# AGCON.net
KiCad netlist of a schematic drawn in EAGLE
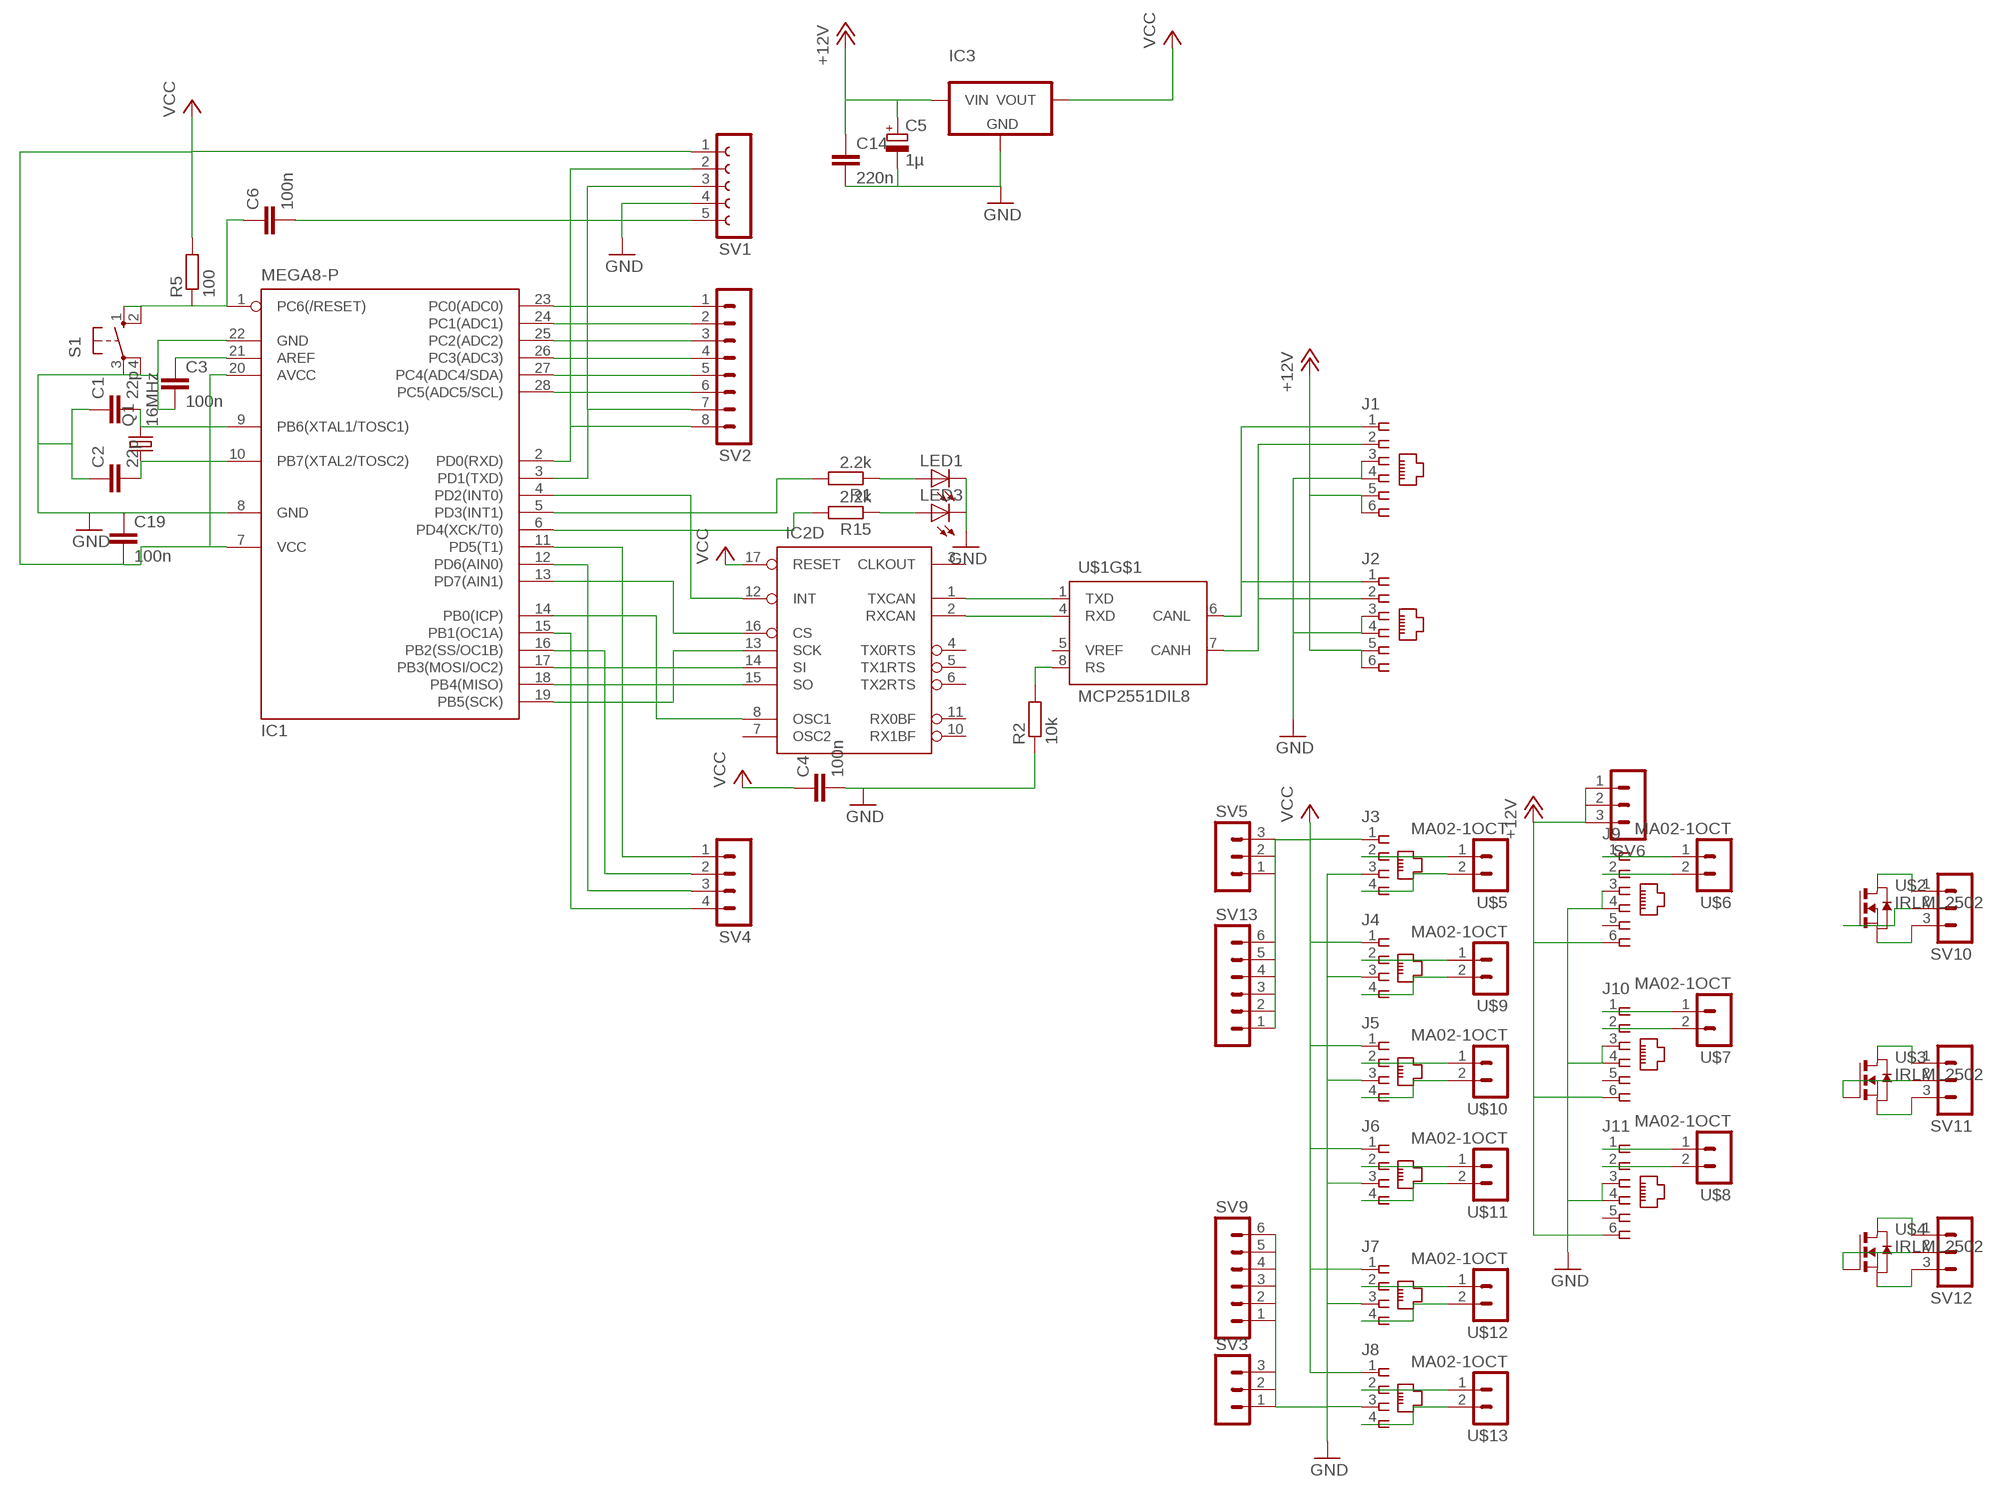
[diagram p0: schematic, sheet 1]

(export (version "E")
  (design (tool "Eeschema 10.0.6"))
  (components
    (comp (ref "C1")
      (value "22p")
      (footprint "eagle-import:C025-024X044")
      (libsource (lib "eagle-import") (part "resistor_C-EU025-024X044"))
    )
    (comp (ref "C2")
      (value "22p")
      (footprint "eagle-import:C025-024X044")
      (libsource (lib "eagle-import") (part "resistor_C-EU025-024X044"))
    )
    (comp (ref "C3")
      (value "100n")
      (footprint "eagle-import:C050-024X044")
      (libsource (lib "eagle-import") (part "C-EU050-024X044"))
    )
    (comp (ref "C4")
      (value "100n")
      (footprint "eagle-import:C050-024X044")
      (libsource (lib "eagle-import") (part "C-EU050-024X044"))
    )
    (comp (ref "C5")
      (value "1µ")
      (footprint "eagle-import:E5-10,5")
      (libsource (lib "eagle-import") (part "CPOL-EUE5-10.5"))
    )
    (comp (ref "C6")
      (value "100n")
      (footprint "eagle-import:C050-024X044")
      (libsource (lib "eagle-import") (part "C-EU050-024X044"))
    )
    (comp (ref "C14")
      (value "220n")
      (footprint "eagle-import:C050-024X044")
      (libsource (lib "eagle-import") (part "C-EU050-024X044"))
    )
    (comp (ref "C19")
      (value "100n")
      (footprint "eagle-import:C050-024X044")
      (libsource (lib "eagle-import") (part "C-EU050-024X044"))
    )
    (comp (ref "IC1")
      (value "MEGA8-P")
      (footprint "eagle-import:DIL28-3")
      (libsource (lib "eagle-import") (part "MEGA8-P"))
    )
    (comp (ref "IC2")
      (value "MCP2515P")
      (footprint "eagle-import:DIL18")
      (libsource (lib "eagle-import") (part "MCP2515P"))
    )
    (comp (ref "IC3")
      (value "MCP1702")
      (footprint "eagle-import:TO-92")
      (libsource (lib "eagle-import") (part "MCP1702"))
    )
    (comp (ref "J1")
      (value "520250-3")
      (footprint "eagle-import:520250-3")
      (libsource (lib "eagle-import") (part "520250-3"))
    )
    (comp (ref "J2")
      (value "520250-3")
      (footprint "eagle-import:520250-3")
      (libsource (lib "eagle-import") (part "520250-3"))
    )
    (comp (ref "J3")
      (value "520249-2")
      (footprint "eagle-import:520249-2")
      (libsource (lib "eagle-import") (part "520249-2"))
    )
    (comp (ref "J4")
      (value "520249-2")
      (footprint "eagle-import:520249-2")
      (libsource (lib "eagle-import") (part "520249-2"))
    )
    (comp (ref "J5")
      (value "520249-2")
      (footprint "eagle-import:520249-2")
      (libsource (lib "eagle-import") (part "520249-2"))
    )
    (comp (ref "J6")
      (value "520249-2")
      (footprint "eagle-import:520249-2")
      (libsource (lib "eagle-import") (part "520249-2"))
    )
    (comp (ref "J7")
      (value "520249-2")
      (footprint "eagle-import:520249-2")
      (libsource (lib "eagle-import") (part "520249-2"))
    )
    (comp (ref "J8")
      (value "520249-2")
      (footprint "eagle-import:520249-2")
      (libsource (lib "eagle-import") (part "520249-2"))
    )
    (comp (ref "J9")
      (value "520250-3")
      (footprint "eagle-import:520250-3")
      (libsource (lib "eagle-import") (part "520250-3"))
    )
    (comp (ref "J10")
      (value "520250-3")
      (footprint "eagle-import:520250-3")
      (libsource (lib "eagle-import") (part "520250-3"))
    )
    (comp (ref "J11")
      (value "520250-3")
      (footprint "eagle-import:520250-3")
      (libsource (lib "eagle-import") (part "520250-3"))
    )
    (comp (ref "LED1")
      (value "LED3MM")
      (footprint "eagle-import:LED3MM")
      (libsource (lib "eagle-import") (part "LED3MM"))
    )
    (comp (ref "LED3")
      (value "LED3MM")
      (footprint "eagle-import:LED3MM")
      (libsource (lib "eagle-import") (part "LED3MM"))
    )
    (comp (ref "Q1")
      (value "16MHz")
      (footprint "eagle-import:HC18U-V")
      (libsource (lib "eagle-import") (part "CRYSTALHC18U-V"))
    )
    (comp (ref "R1")
      (value "2.2k")
      (footprint "eagle-import:0207_7")
      (libsource (lib "eagle-import") (part "R-EU_0207/7"))
    )
    (comp (ref "R2")
      (value "10k")
      (footprint "eagle-import:0207_7")
      (libsource (lib "eagle-import") (part "R-EU_0207/7"))
    )
    (comp (ref "R5")
      (value "100")
      (footprint "eagle-import:0207_7")
      (libsource (lib "eagle-import") (part "R-EU_0207/7"))
    )
    (comp (ref "R15")
      (value "2.2k")
      (footprint "eagle-import:0207_7")
      (libsource (lib "eagle-import") (part "R-EU_0207/7"))
    )
    (comp (ref "S1")
      (value "10-XX")
      (footprint "eagle-import:B3F-10XX")
      (fields (field (name "MPN") "B3F-1000"))
      (libsource (lib "eagle-import") (part "10-XX"))
    )
    (comp (ref "SV1")
      (value "FE05-1")
      (footprint "eagle-import:FE05-1")
      (libsource (lib "eagle-import") (part "FE05-1"))
    )
    (comp (ref "SV2")
      (value "MA08-1OCT")
      (footprint "eagle-import:MA08-1OCT")
      (libsource (lib "eagle-import") (part "MA08-1OCT"))
    )
    (comp (ref "SV3")
      (value "MA03-1OCT")
      (footprint "eagle-import:MA03-1OCT")
      (libsource (lib "eagle-import") (part "MA03-1OCT"))
    )
    (comp (ref "SV4")
      (value "MA04-1OCT")
      (footprint "eagle-import:MA04-1OCT")
      (libsource (lib "eagle-import") (part "MA04-1OCT"))
    )
    (comp (ref "SV5")
      (value "MA03-1OCT")
      (footprint "eagle-import:MA03-1OCT")
      (libsource (lib "eagle-import") (part "MA03-1OCT"))
    )
    (comp (ref "SV6")
      (value "MA03-1OCT")
      (footprint "eagle-import:MA03-1OCT")
      (libsource (lib "eagle-import") (part "MA03-1OCT"))
    )
    (comp (ref "SV9")
      (value "MA06-1MA06-1OCT")
      (footprint "eagle-import:MA06-1OCT")
      (libsource (lib "eagle-import") (part "MA06-1MA06-1OCT"))
    )
    (comp (ref "SV10")
      (value "MA03-1OCT")
      (footprint "eagle-import:MA03-1OCT")
      (libsource (lib "eagle-import") (part "MA03-1OCT"))
    )
    (comp (ref "SV11")
      (value "MA03-1OCT")
      (footprint "eagle-import:MA03-1OCT")
      (libsource (lib "eagle-import") (part "MA03-1OCT"))
    )
    (comp (ref "SV12")
      (value "MA03-1OCT")
      (footprint "eagle-import:MA03-1OCT")
      (libsource (lib "eagle-import") (part "MA03-1OCT"))
    )
    (comp (ref "SV13")
      (value "MA06-1MA06-1OCT")
      (footprint "eagle-import:MA06-1OCT")
      (libsource (lib "eagle-import") (part "MA06-1MA06-1OCT"))
    )
    (comp (ref "U$1")
      (value "MCP2551DIL8")
      (footprint "eagle-import:DIL08")
      (libsource (lib "eagle-import") (part "MCP2551DIL8"))
    )
    (comp (ref "U$2")
      (value "IRLML2502")
      (footprint "eagle-import:SOT-23")
      (libsource (lib "eagle-import") (part "IRLML2502"))
    )
    (comp (ref "U$3")
      (value "IRLML2502")
      (footprint "eagle-import:SOT-23")
      (libsource (lib "eagle-import") (part "IRLML2502"))
    )
    (comp (ref "U$4")
      (value "IRLML2502")
      (footprint "eagle-import:SOT-23")
      (libsource (lib "eagle-import") (part "IRLML2502"))
    )
    (comp (ref "U$5")
      (value "MA02-1OCT")
      (footprint "eagle-import:MA02-1OCT")
      (libsource (lib "eagle-import") (part "MA02-1OCT"))
    )
    (comp (ref "U$6")
      (value "MA02-1OCT")
      (footprint "eagle-import:MA02-1OCT")
      (libsource (lib "eagle-import") (part "MA02-1OCT"))
    )
    (comp (ref "U$7")
      (value "MA02-1OCT")
      (footprint "eagle-import:MA02-1OCT")
      (libsource (lib "eagle-import") (part "MA02-1OCT"))
    )
    (comp (ref "U$8")
      (value "MA02-1OCT")
      (footprint "eagle-import:MA02-1OCT")
      (libsource (lib "eagle-import") (part "MA02-1OCT"))
    )
    (comp (ref "U$9")
      (value "MA02-1OCT")
      (footprint "eagle-import:MA02-1OCT")
      (libsource (lib "eagle-import") (part "MA02-1OCT"))
    )
    (comp (ref "U$10")
      (value "MA02-1OCT")
      (footprint "eagle-import:MA02-1OCT")
      (libsource (lib "eagle-import") (part "MA02-1OCT"))
    )
    (comp (ref "U$11")
      (value "MA02-1OCT")
      (footprint "eagle-import:MA02-1OCT")
      (libsource (lib "eagle-import") (part "MA02-1OCT"))
    )
    (comp (ref "U$12")
      (value "MA02-1OCT")
      (footprint "eagle-import:MA02-1OCT")
      (libsource (lib "eagle-import") (part "MA02-1OCT"))
    )
    (comp (ref "U$13")
      (value "MA02-1OCT")
      (footprint "eagle-import:MA02-1OCT")
      (libsource (lib "eagle-import") (part "MA02-1OCT"))
    )
  )
  (nets
    (net (code "1") (name "+12V") (class "Default")
      (node (ref "C14") (pin "1") (pinfunction "1_1") (pintype "passive"))
      (node (ref "C5") (pin "+") (pinfunction "+_+") (pintype "passive"))
      (node (ref "IC3") (pin "2") (pinfunction "VIN_2") (pintype "input"))
      (node (ref "J1") (pin "5") (pinfunction "5_5") (pintype "passive"))
      (node (ref "J1") (pin "6") (pinfunction "6_6") (pintype "passive"))
      (node (ref "J10") (pin "6") (pinfunction "6_6") (pintype "passive"))
      (node (ref "J11") (pin "6") (pinfunction "6_6") (pintype "passive"))
      (node (ref "J2") (pin "5") (pinfunction "5_5") (pintype "passive"))
      (node (ref "J2") (pin "6") (pinfunction "6_6") (pintype "passive"))
      (node (ref "J9") (pin "6") (pinfunction "6_6") (pintype "passive"))
      (node (ref "SV6") (pin "1") (pinfunction "1_1") (pintype "passive"))
      (node (ref "SV6") (pin "2") (pinfunction "2_2") (pintype "passive"))
      (node (ref "SV6") (pin "3") (pinfunction "3_3") (pintype "passive"))
    )
    (net (code "2") (name "GND") (class "Default")
      (node (ref "C1") (pin "1") (pinfunction "1_1") (pintype "passive"))
      (node (ref "C14") (pin "2") (pinfunction "2_2") (pintype "passive"))
      (node (ref "C19") (pin "1") (pinfunction "1_1") (pintype "passive"))
      (node (ref "C2") (pin "1") (pinfunction "1_1") (pintype "passive"))
      (node (ref "C3") (pin "2") (pinfunction "2_2") (pintype "passive"))
      (node (ref "C4") (pin "2") (pinfunction "2_2") (pintype "passive"))
      (node (ref "C5") (pin "-") (pinfunction "-_-") (pintype "passive"))
      (node (ref "IC1") (pin "22") (pinfunction "GND_22") (pintype "power_in"))
      (node (ref "IC1") (pin "8") (pinfunction "GND_8") (pintype "power_in"))
      (node (ref "IC3") (pin "1") (pinfunction "GND_1") (pintype "passive"))
      (node (ref "J1") (pin "3") (pinfunction "3_3") (pintype "passive"))
      (node (ref "J1") (pin "4") (pinfunction "4_4") (pintype "passive"))
      (node (ref "J10") (pin "3") (pinfunction "3_3") (pintype "passive"))
      (node (ref "J10") (pin "4") (pinfunction "4_4") (pintype "passive"))
      (node (ref "J11") (pin "3") (pinfunction "3_3") (pintype "passive"))
      (node (ref "J11") (pin "4") (pinfunction "4_4") (pintype "passive"))
      (node (ref "J2") (pin "3") (pinfunction "3_3") (pintype "passive"))
      (node (ref "J2") (pin "4") (pinfunction "4_4") (pintype "passive"))
      (node (ref "J3") (pin "3") (pinfunction "3_3") (pintype "passive"))
      (node (ref "J4") (pin "3") (pinfunction "3_3") (pintype "passive"))
      (node (ref "J5") (pin "3") (pinfunction "3_3") (pintype "passive"))
      (node (ref "J6") (pin "3") (pinfunction "3_3") (pintype "passive"))
      (node (ref "J7") (pin "3") (pinfunction "3_3") (pintype "passive"))
      (node (ref "J8") (pin "3") (pinfunction "3_3") (pintype "passive"))
      (node (ref "J9") (pin "3") (pinfunction "3_3") (pintype "passive"))
      (node (ref "J9") (pin "4") (pinfunction "4_4") (pintype "passive"))
      (node (ref "LED1") (pin "K") (pinfunction "C_K") (pintype "passive"))
      (node (ref "LED3") (pin "K") (pinfunction "C_K") (pintype "passive"))
      (node (ref "R2") (pin "1") (pinfunction "1_1") (pintype "passive"))
      (node (ref "S1") (pin "3") (pinfunction "P_3") (pintype "passive"))
      (node (ref "S1") (pin "4") (pinfunction "P1_4") (pintype "passive"))
      (node (ref "SV1") (pin "4") (pinfunction "4_4") (pintype "passive"))
      (node (ref "SV3") (pin "1") (pinfunction "1_1") (pintype "passive"))
      (node (ref "SV3") (pin "2") (pinfunction "2_2") (pintype "passive"))
      (node (ref "SV3") (pin "3") (pinfunction "3_3") (pintype "passive"))
      (node (ref "SV9") (pin "1") (pinfunction "1_1") (pintype "passive"))
      (node (ref "SV9") (pin "2") (pinfunction "2_2") (pintype "passive"))
      (node (ref "SV9") (pin "3") (pinfunction "3_3") (pintype "passive"))
      (node (ref "SV9") (pin "4") (pinfunction "4_4") (pintype "passive"))
      (node (ref "SV9") (pin "5") (pinfunction "5_5") (pintype "passive"))
      (node (ref "SV9") (pin "6") (pinfunction "6_6") (pintype "passive"))
    )
    (net (code "3") (name "Net-(C6-Pad2)") (class "Default")
      (node (ref "C6") (pin "2") (pinfunction "2_2") (pintype "passive"))
      (node (ref "SV1") (pin "5") (pinfunction "5_5") (pintype "passive"))
    )
    (net (code "4") (name "Net-(IC1-AREF)") (class "Default")
      (node (ref "C3") (pin "1") (pinfunction "1_1") (pintype "passive"))
      (node (ref "IC1") (pin "21") (pinfunction "AREF_21") (pintype "passive"))
    )
    (net (code "5") (name "Net-(IC1-PB0(ICP))") (class "Default")
      (node (ref "IC1") (pin "14") (pinfunction "PB0(ICP)_14") (pintype "bidirectional"))
      (node (ref "IC2") (pin "8") (pinfunction "OSC1_8") (pintype "input"))
    )
    (net (code "6") (name "Net-(IC1-PB1(OC1A))") (class "Default")
      (node (ref "IC1") (pin "15") (pinfunction "PB1(OC1A)_15") (pintype "bidirectional"))
      (node (ref "SV4") (pin "4") (pinfunction "4_4") (pintype "passive"))
    )
    (net (code "7") (name "Net-(IC1-PB2(SS{slash}OC1B))") (class "Default")
      (node (ref "IC1") (pin "16") (pinfunction "PB2(SS/OC1B)_16") (pintype "bidirectional"))
      (node (ref "SV4") (pin "2") (pinfunction "2_2") (pintype "passive"))
    )
    (net (code "8") (name "Net-(IC1-PB3(MOSI{slash}OC2))") (class "Default")
      (node (ref "IC1") (pin "17") (pinfunction "PB3(MOSI/OC2)_17") (pintype "bidirectional"))
      (node (ref "IC2") (pin "14") (pinfunction "SI_14") (pintype "input"))
    )
    (net (code "9") (name "Net-(IC1-PB4(MISO))") (class "Default")
      (node (ref "IC1") (pin "18") (pinfunction "PB4(MISO)_18") (pintype "bidirectional"))
      (node (ref "IC2") (pin "15") (pinfunction "SO_15") (pintype "output"))
    )
    (net (code "10") (name "Net-(IC1-PB5(SCK))") (class "Default")
      (node (ref "IC1") (pin "19") (pinfunction "PB5(SCK)_19") (pintype "bidirectional"))
      (node (ref "IC2") (pin "13") (pinfunction "SCK_13") (pintype "input"))
    )
    (net (code "11") (name "Net-(IC1-PB6(XTAL1{slash}TOSC1))") (class "Default")
      (node (ref "C1") (pin "2") (pinfunction "2_2") (pintype "passive"))
      (node (ref "IC1") (pin "9") (pinfunction "PB6(XTAL1/TOSC1)_9") (pintype "bidirectional"))
      (node (ref "Q1") (pin "2") (pinfunction "2_2") (pintype "passive"))
    )
    (net (code "12") (name "Net-(IC1-PB7(XTAL2{slash}TOSC2))") (class "Default")
      (node (ref "C2") (pin "2") (pinfunction "2_2") (pintype "passive"))
      (node (ref "IC1") (pin "10") (pinfunction "PB7(XTAL2/TOSC2)_10") (pintype "bidirectional"))
      (node (ref "Q1") (pin "1") (pinfunction "1_1") (pintype "passive"))
    )
    (net (code "13") (name "Net-(IC1-PC0(ADC0))") (class "Default")
      (node (ref "IC1") (pin "23") (pinfunction "PC0(ADC0)_23") (pintype "bidirectional"))
      (node (ref "SV2") (pin "1") (pinfunction "1_1") (pintype "passive"))
    )
    (net (code "14") (name "Net-(IC1-PC1(ADC1))") (class "Default")
      (node (ref "IC1") (pin "24") (pinfunction "PC1(ADC1)_24") (pintype "bidirectional"))
      (node (ref "SV2") (pin "2") (pinfunction "2_2") (pintype "passive"))
    )
    (net (code "15") (name "Net-(IC1-PC2(ADC2))") (class "Default")
      (node (ref "IC1") (pin "25") (pinfunction "PC2(ADC2)_25") (pintype "bidirectional"))
      (node (ref "SV2") (pin "3") (pinfunction "3_3") (pintype "passive"))
    )
    (net (code "16") (name "Net-(IC1-PC3(ADC3))") (class "Default")
      (node (ref "IC1") (pin "26") (pinfunction "PC3(ADC3)_26") (pintype "bidirectional"))
      (node (ref "SV2") (pin "4") (pinfunction "4_4") (pintype "passive"))
    )
    (net (code "17") (name "Net-(IC1-PC4(ADC4{slash}SDA))") (class "Default")
      (node (ref "IC1") (pin "27") (pinfunction "PC4(ADC4/SDA)_27") (pintype "bidirectional"))
      (node (ref "SV2") (pin "5") (pinfunction "5_5") (pintype "passive"))
    )
    (net (code "18") (name "Net-(IC1-PC5(ADC5{slash}SCL))") (class "Default")
      (node (ref "IC1") (pin "28") (pinfunction "PC5(ADC5/SCL)_28") (pintype "bidirectional"))
      (node (ref "SV2") (pin "6") (pinfunction "6_6") (pintype "passive"))
    )
    (net (code "19") (name "Net-(IC1-PC6({slash}RESET))") (class "Default")
      (node (ref "C6") (pin "1") (pinfunction "1_1") (pintype "passive"))
      (node (ref "IC1") (pin "1") (pinfunction "PC6(/RESET)_1") (pintype "bidirectional"))
      (node (ref "R5") (pin "1") (pinfunction "1_1") (pintype "passive"))
      (node (ref "S1") (pin "1") (pinfunction "S_1") (pintype "passive"))
      (node (ref "S1") (pin "2") (pinfunction "S1_2") (pintype "passive"))
    )
    (net (code "20") (name "Net-(IC1-PD0(RXD))") (class "Default")
      (node (ref "IC1") (pin "2") (pinfunction "PD0(RXD)_2") (pintype "bidirectional"))
      (node (ref "SV1") (pin "2") (pinfunction "2_2") (pintype "passive"))
      (node (ref "SV2") (pin "8") (pinfunction "8_8") (pintype "passive"))
    )
    (net (code "21") (name "Net-(IC1-PD1(TXD))") (class "Default")
      (node (ref "IC1") (pin "3") (pinfunction "PD1(TXD)_3") (pintype "bidirectional"))
      (node (ref "SV1") (pin "3") (pinfunction "3_3") (pintype "passive"))
      (node (ref "SV2") (pin "7") (pinfunction "7_7") (pintype "passive"))
    )
    (net (code "22") (name "Net-(IC1-PD2(INT0))") (class "Default")
      (node (ref "IC1") (pin "4") (pinfunction "PD2(INT0)_4") (pintype "bidirectional"))
      (node (ref "IC2") (pin "12") (pinfunction "INT_12") (pintype "output"))
    )
    (net (code "23") (name "Net-(IC1-PD3(INT1))") (class "Default")
      (node (ref "IC1") (pin "5") (pinfunction "PD3(INT1)_5") (pintype "bidirectional"))
      (node (ref "R1") (pin "2") (pinfunction "2_2") (pintype "passive"))
    )
    (net (code "24") (name "Net-(IC1-PD4(XCK{slash}T0))") (class "Default")
      (node (ref "IC1") (pin "6") (pinfunction "PD4(XCK/T0)_6") (pintype "bidirectional"))
      (node (ref "R15") (pin "2") (pinfunction "2_2") (pintype "passive"))
    )
    (net (code "25") (name "Net-(IC1-PD5(T1))") (class "Default")
      (node (ref "IC1") (pin "11") (pinfunction "PD5(T1)_11") (pintype "bidirectional"))
      (node (ref "SV4") (pin "1") (pinfunction "1_1") (pintype "passive"))
    )
    (net (code "26") (name "Net-(IC1-PD6(AIN0))") (class "Default")
      (node (ref "IC1") (pin "12") (pinfunction "PD6(AIN0)_12") (pintype "bidirectional"))
      (node (ref "SV4") (pin "3") (pinfunction "3_3") (pintype "passive"))
    )
    (net (code "27") (name "Net-(IC1-PD7(AIN1))") (class "Default")
      (node (ref "IC1") (pin "13") (pinfunction "PD7(AIN1)_13") (pintype "bidirectional"))
      (node (ref "IC2") (pin "16") (pinfunction "CS_16") (pintype "input"))
    )
    (net (code "28") (name "Net-(IC2A-RXCAN)") (class "Default")
      (node (ref "IC2") (pin "2") (pinfunction "RXCAN_2") (pintype "input"))
      (node (ref "U$1") (pin "4") (pinfunction "RXD_4") (pintype "bidirectional"))
    )
    (net (code "29") (name "Net-(IC2A-TXCAN)") (class "Default")
      (node (ref "IC2") (pin "1") (pinfunction "TXCAN_1") (pintype "output"))
      (node (ref "U$1") (pin "1") (pinfunction "TXD_1") (pintype "bidirectional"))
    )
    (net (code "30") (name "Net-(J3-Pad2)") (class "Default")
      (node (ref "J3") (pin "2") (pinfunction "2_2") (pintype "passive"))
      (node (ref "U$5") (pin "1") (pinfunction "1_1") (pintype "passive"))
    )
    (net (code "31") (name "Net-(J3-Pad4)") (class "Default")
      (node (ref "J3") (pin "4") (pinfunction "4_4") (pintype "passive"))
      (node (ref "U$5") (pin "2") (pinfunction "2_2") (pintype "passive"))
    )
    (net (code "32") (name "Net-(J4-Pad2)") (class "Default")
      (node (ref "J4") (pin "2") (pinfunction "2_2") (pintype "passive"))
      (node (ref "U$9") (pin "1") (pinfunction "1_1") (pintype "passive"))
    )
    (net (code "33") (name "Net-(J4-Pad4)") (class "Default")
      (node (ref "J4") (pin "4") (pinfunction "4_4") (pintype "passive"))
      (node (ref "U$9") (pin "2") (pinfunction "2_2") (pintype "passive"))
    )
    (net (code "34") (name "Net-(J5-Pad2)") (class "Default")
      (node (ref "J5") (pin "2") (pinfunction "2_2") (pintype "passive"))
      (node (ref "U$10") (pin "1") (pinfunction "1_1") (pintype "passive"))
    )
    (net (code "35") (name "Net-(J5-Pad4)") (class "Default")
      (node (ref "J5") (pin "4") (pinfunction "4_4") (pintype "passive"))
      (node (ref "U$10") (pin "2") (pinfunction "2_2") (pintype "passive"))
    )
    (net (code "36") (name "Net-(J6-Pad2)") (class "Default")
      (node (ref "J6") (pin "2") (pinfunction "2_2") (pintype "passive"))
      (node (ref "U$11") (pin "1") (pinfunction "1_1") (pintype "passive"))
    )
    (net (code "37") (name "Net-(J6-Pad4)") (class "Default")
      (node (ref "J6") (pin "4") (pinfunction "4_4") (pintype "passive"))
      (node (ref "U$11") (pin "2") (pinfunction "2_2") (pintype "passive"))
    )
    (net (code "38") (name "Net-(J7-Pad2)") (class "Default")
      (node (ref "J7") (pin "2") (pinfunction "2_2") (pintype "passive"))
      (node (ref "U$12") (pin "1") (pinfunction "1_1") (pintype "passive"))
    )
    (net (code "39") (name "Net-(J7-Pad4)") (class "Default")
      (node (ref "J7") (pin "4") (pinfunction "4_4") (pintype "passive"))
      (node (ref "U$12") (pin "2") (pinfunction "2_2") (pintype "passive"))
    )
    (net (code "40") (name "Net-(J8-Pad2)") (class "Default")
      (node (ref "J8") (pin "2") (pinfunction "2_2") (pintype "passive"))
      (node (ref "U$13") (pin "1") (pinfunction "1_1") (pintype "passive"))
    )
    (net (code "41") (name "Net-(J8-Pad4)") (class "Default")
      (node (ref "J8") (pin "4") (pinfunction "4_4") (pintype "passive"))
      (node (ref "U$13") (pin "2") (pinfunction "2_2") (pintype "passive"))
    )
    (net (code "42") (name "Net-(J9-Pad1)") (class "Default")
      (node (ref "J9") (pin "1") (pinfunction "1_1") (pintype "passive"))
      (node (ref "U$6") (pin "1") (pinfunction "1_1") (pintype "passive"))
    )
    (net (code "43") (name "Net-(J9-Pad2)") (class "Default")
      (node (ref "J9") (pin "2") (pinfunction "2_2") (pintype "passive"))
      (node (ref "U$6") (pin "2") (pinfunction "2_2") (pintype "passive"))
    )
    (net (code "44") (name "Net-(J10-Pad1)") (class "Default")
      (node (ref "J10") (pin "1") (pinfunction "1_1") (pintype "passive"))
      (node (ref "U$7") (pin "1") (pinfunction "1_1") (pintype "passive"))
    )
    (net (code "45") (name "Net-(J10-Pad2)") (class "Default")
      (node (ref "J10") (pin "2") (pinfunction "2_2") (pintype "passive"))
      (node (ref "U$7") (pin "2") (pinfunction "2_2") (pintype "passive"))
    )
    (net (code "46") (name "Net-(J11-Pad1)") (class "Default")
      (node (ref "J11") (pin "1") (pinfunction "1_1") (pintype "passive"))
      (node (ref "U$8") (pin "1") (pinfunction "1_1") (pintype "passive"))
    )
    (net (code "47") (name "Net-(J11-Pad2)") (class "Default")
      (node (ref "J11") (pin "2") (pinfunction "2_2") (pintype "passive"))
      (node (ref "U$8") (pin "2") (pinfunction "2_2") (pintype "passive"))
    )
    (net (code "48") (name "Net-(LED1-PadA)") (class "Default")
      (node (ref "LED1") (pin "A") (pinfunction "A_A") (pintype "passive"))
      (node (ref "R1") (pin "1") (pinfunction "1_1") (pintype "passive"))
    )
    (net (code "49") (name "Net-(LED3-PadA)") (class "Default")
      (node (ref "LED3") (pin "A") (pinfunction "A_A") (pintype "passive"))
      (node (ref "R15") (pin "1") (pinfunction "1_1") (pintype "passive"))
    )
    (net (code "50") (name "Net-(U$1A-CANH)") (class "Default")
      (node (ref "J1") (pin "2") (pinfunction "2_2") (pintype "passive"))
      (node (ref "J2") (pin "2") (pinfunction "2_2") (pintype "passive"))
      (node (ref "U$1") (pin "7") (pinfunction "CANH_7") (pintype "bidirectional"))
    )
    (net (code "51") (name "Net-(U$1A-CANL)") (class "Default")
      (node (ref "J1") (pin "1") (pinfunction "1_1") (pintype "passive"))
      (node (ref "J2") (pin "1") (pinfunction "1_1") (pintype "passive"))
      (node (ref "U$1") (pin "6") (pinfunction "CANL_6") (pintype "bidirectional"))
    )
    (net (code "52") (name "Net-(U$1A-RS)") (class "Default")
      (node (ref "R2") (pin "2") (pinfunction "2_2") (pintype "passive"))
      (node (ref "U$1") (pin "8") (pinfunction "RS_8") (pintype "bidirectional"))
    )
    (net (code "53") (name "Net-(U$2-D)") (class "Default")
      (node (ref "SV10") (pin "1") (pinfunction "1_1") (pintype "passive"))
      (node (ref "U$2") (pin "3") (pinfunction "D_3") (pintype "passive"))
    )
    (net (code "54") (name "Net-(U$2-G)") (class "Default")
      (node (ref "SV10") (pin "2") (pinfunction "2_2") (pintype "passive"))
      (node (ref "U$2") (pin "1") (pinfunction "G_1") (pintype "passive"))
    )
    (net (code "55") (name "Net-(U$2-S)") (class "Default")
      (node (ref "SV10") (pin "3") (pinfunction "3_3") (pintype "passive"))
      (node (ref "U$2") (pin "2") (pinfunction "S_2") (pintype "passive"))
    )
    (net (code "56") (name "Net-(U$3-D)") (class "Default")
      (node (ref "SV11") (pin "1") (pinfunction "1_1") (pintype "passive"))
      (node (ref "U$3") (pin "3") (pinfunction "D_3") (pintype "passive"))
    )
    (net (code "57") (name "Net-(U$3-G)") (class "Default")
      (node (ref "SV11") (pin "2") (pinfunction "2_2") (pintype "passive"))
      (node (ref "U$3") (pin "1") (pinfunction "G_1") (pintype "passive"))
    )
    (net (code "58") (name "Net-(U$3-S)") (class "Default")
      (node (ref "SV11") (pin "3") (pinfunction "3_3") (pintype "passive"))
      (node (ref "U$3") (pin "2") (pinfunction "S_2") (pintype "passive"))
    )
    (net (code "59") (name "Net-(U$4-D)") (class "Default")
      (node (ref "SV12") (pin "1") (pinfunction "1_1") (pintype "passive"))
      (node (ref "U$4") (pin "3") (pinfunction "D_3") (pintype "passive"))
    )
    (net (code "60") (name "Net-(U$4-G)") (class "Default")
      (node (ref "SV12") (pin "2") (pinfunction "2_2") (pintype "passive"))
      (node (ref "U$4") (pin "1") (pinfunction "G_1") (pintype "passive"))
    )
    (net (code "61") (name "Net-(U$4-S)") (class "Default")
      (node (ref "SV12") (pin "3") (pinfunction "3_3") (pintype "passive"))
      (node (ref "U$4") (pin "2") (pinfunction "S_2") (pintype "passive"))
    )
    (net (code "62") (name "VCC") (class "Default")
      (node (ref "C19") (pin "2") (pinfunction "2_2") (pintype "passive"))
      (node (ref "C4") (pin "1") (pinfunction "1_1") (pintype "passive"))
      (node (ref "IC1") (pin "20") (pinfunction "AVCC_20") (pintype "power_in"))
      (node (ref "IC1") (pin "7") (pinfunction "VCC_7") (pintype "power_in"))
      (node (ref "IC2") (pin "17") (pinfunction "RESET_17") (pintype "input"))
      (node (ref "IC3") (pin "3") (pinfunction "VOUT_3") (pintype "passive"))
      (node (ref "J3") (pin "1") (pinfunction "1_1") (pintype "passive"))
      (node (ref "J4") (pin "1") (pinfunction "1_1") (pintype "passive"))
      (node (ref "J5") (pin "1") (pinfunction "1_1") (pintype "passive"))
      (node (ref "J6") (pin "1") (pinfunction "1_1") (pintype "passive"))
      (node (ref "J7") (pin "1") (pinfunction "1_1") (pintype "passive"))
      (node (ref "J8") (pin "1") (pinfunction "1_1") (pintype "passive"))
      (node (ref "R5") (pin "2") (pinfunction "2_2") (pintype "passive"))
      (node (ref "SV1") (pin "1") (pinfunction "1_1") (pintype "passive"))
      (node (ref "SV13") (pin "1") (pinfunction "1_1") (pintype "passive"))
      (node (ref "SV13") (pin "2") (pinfunction "2_2") (pintype "passive"))
      (node (ref "SV13") (pin "3") (pinfunction "3_3") (pintype "passive"))
      (node (ref "SV13") (pin "4") (pinfunction "4_4") (pintype "passive"))
      (node (ref "SV13") (pin "5") (pinfunction "5_5") (pintype "passive"))
      (node (ref "SV13") (pin "6") (pinfunction "6_6") (pintype "passive"))
      (node (ref "SV5") (pin "1") (pinfunction "1_1") (pintype "passive"))
      (node (ref "SV5") (pin "2") (pinfunction "2_2") (pintype "passive"))
      (node (ref "SV5") (pin "3") (pinfunction "3_3") (pintype "passive"))
    )
    (net (code "63") (name "unconnected-(IC2A-CLKOUT-Pad3)") (class "Default")
      (node (ref "IC2") (pin "3") (pinfunction "CLKOUT_3") (pintype "output"))
    )
    (net (code "64") (name "unconnected-(IC2A-OSC2-Pad7)") (class "Default")
      (node (ref "IC2") (pin "7") (pinfunction "OSC2_7") (pintype "input"))
    )
    (net (code "65") (name "unconnected-(IC2A-RX0BF-Pad11)") (class "Default")
      (node (ref "IC2") (pin "11") (pinfunction "RX0BF_11") (pintype "output"))
    )
    (net (code "66") (name "unconnected-(IC2A-RX1BF-Pad10)") (class "Default")
      (node (ref "IC2") (pin "10") (pinfunction "RX1BF_10") (pintype "output"))
    )
    (net (code "67") (name "unconnected-(IC2A-TX0RTS-Pad4)") (class "Default")
      (node (ref "IC2") (pin "4") (pinfunction "TX0RTS_4") (pintype "input"))
    )
    (net (code "68") (name "unconnected-(IC2A-TX1RTS-Pad5)") (class "Default")
      (node (ref "IC2") (pin "5") (pinfunction "TX1RTS_5") (pintype "input"))
    )
    (net (code "69") (name "unconnected-(IC2A-TX2RTS-Pad6)") (class "Default")
      (node (ref "IC2") (pin "6") (pinfunction "TX2RTS_6") (pintype "input"))
    )
    (net (code "70") (name "unconnected-(J9-Pad5)") (class "Default")
      (node (ref "J9") (pin "5") (pinfunction "5_5") (pintype "passive"))
    )
    (net (code "71") (name "unconnected-(J10-Pad5)") (class "Default")
      (node (ref "J10") (pin "5") (pinfunction "5_5") (pintype "passive"))
    )
    (net (code "72") (name "unconnected-(J11-Pad5)") (class "Default")
      (node (ref "J11") (pin "5") (pinfunction "5_5") (pintype "passive"))
    )
    (net (code "73") (name "unconnected-(U$1A-VREF-Pad5)") (class "Default")
      (node (ref "U$1") (pin "5") (pinfunction "VREF_5") (pintype "bidirectional"))
    )
  )
)
